# AD9854.net
KiCad netlist of a schematic drawn in Altium Designer
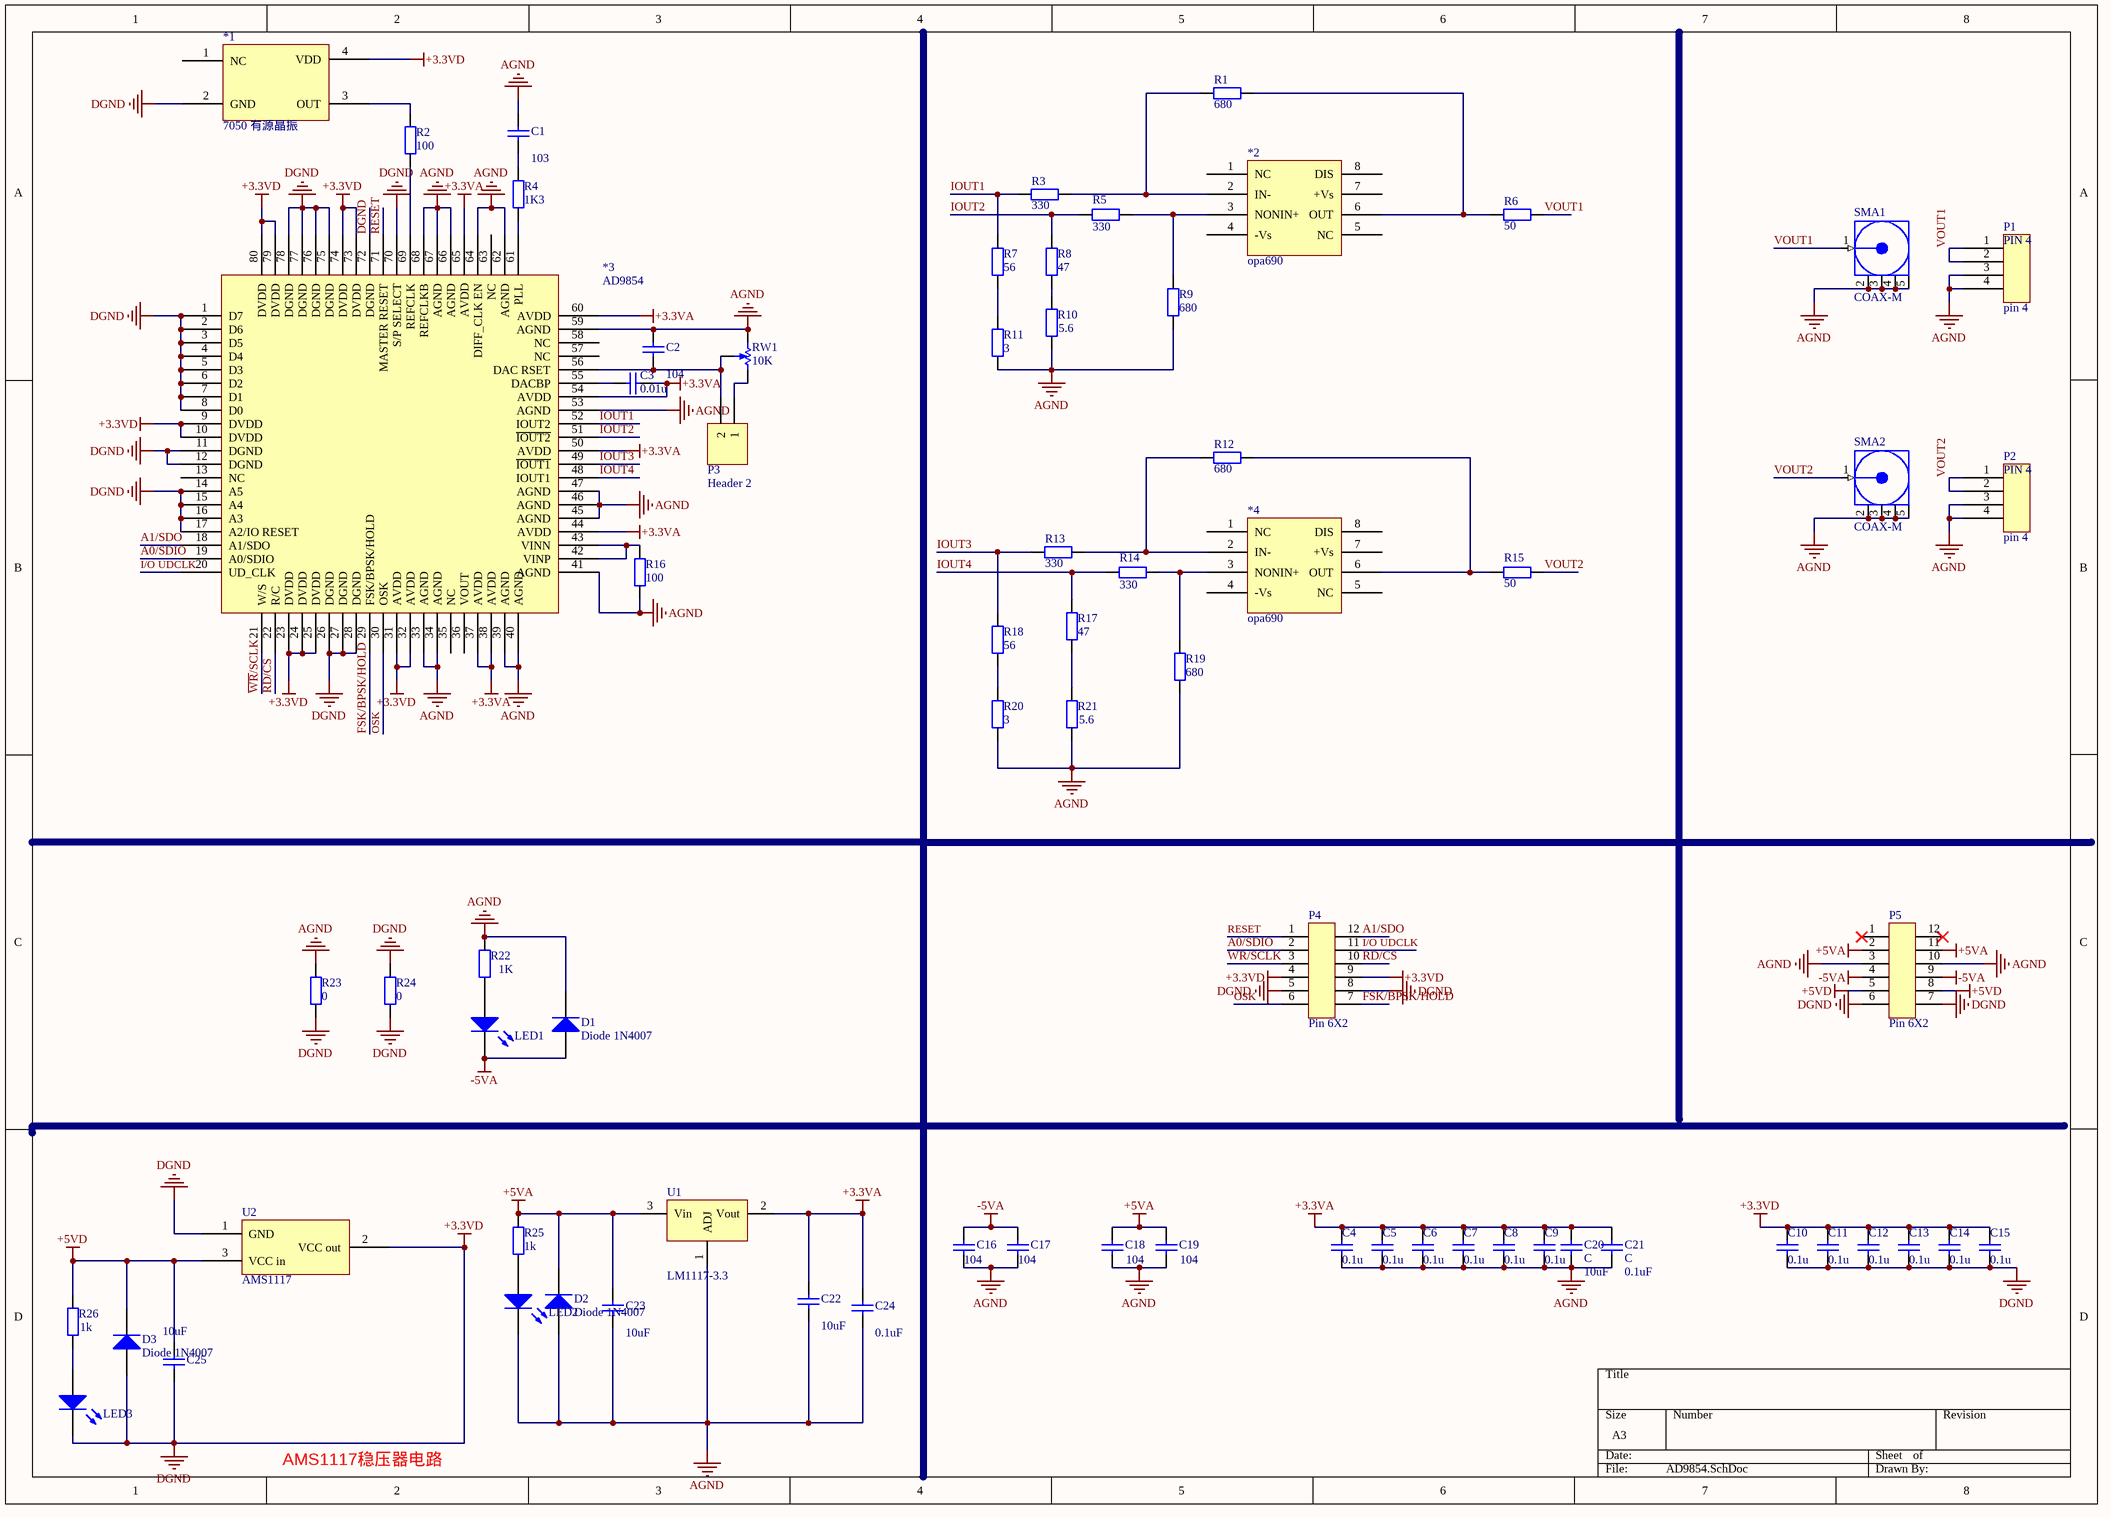
[diagram p0: AD9854.SchDoc]

(export (version "E")
  (design (tool "Eeschema 10.0.6"))
  (components
    (comp (ref "*1") (value "7050 有源晶振") (footprint "7050晶振") (libsource (lib "我的元件库") (part "7050 有源晶振")))
    (comp (ref "*2") (value "opa690") (footprint "OPA690") (libsource (lib "JC") (part "opa690")))
    (comp (ref "*3") (value "AD9854") (footprint "LPQF 80 9854") (libsource (lib "我的元件库") (part "AD9854")))
    (comp (ref "*4") (value "opa690") (footprint "OPA690") (libsource (lib "JC") (part "opa690")))
    (comp (ref "C1")
      (value "103")
      (footprint "C0603")
      (fields (field (name "Comment") "C"))
      (libsource (lib "我的元件库") (part "C"))
    )
    (comp (ref "C2")
      (value "104")
      (footprint "C0603")
      (fields (field (name "Comment") "C"))
      (libsource (lib "我的元件库") (part "C"))
    )
    (comp (ref "C3") (value "0.01u") (footprint "C0603") (libsource (lib "顶层SMD") (part "C_0805")))
    (comp (ref "C4") (value "0.1u") (footprint "C0603") (libsource (lib "顶层SMD") (part "C_0805")))
    (comp (ref "C5") (value "0.1u") (footprint "C0603") (libsource (lib "顶层SMD") (part "C_0805")))
    (comp (ref "C6") (value "0.1u") (footprint "C0603") (libsource (lib "顶层SMD") (part "C_0805")))
    (comp (ref "C7") (value "0.1u") (footprint "C0603") (libsource (lib "顶层SMD") (part "C_0805")))
    (comp (ref "C8") (value "0.1u") (footprint "C0603") (libsource (lib "顶层SMD") (part "C_0805")))
    (comp (ref "C9") (value "0.1u") (footprint "C0603") (libsource (lib "顶层SMD") (part "C_0805")))
    (comp (ref "C10") (value "0.1u") (footprint "C0603") (libsource (lib "顶层SMD") (part "C_0805")))
    (comp (ref "C11") (value "0.1u") (footprint "C0603") (libsource (lib "顶层SMD") (part "C_0805")))
    (comp (ref "C12") (value "0.1u") (footprint "C0603") (libsource (lib "顶层SMD") (part "C_0805")))
    (comp (ref "C13") (value "0.1u") (footprint "C0603") (libsource (lib "顶层SMD") (part "C_0805")))
    (comp (ref "C14") (value "0.1u") (footprint "C0603") (libsource (lib "顶层SMD") (part "C_0805")))
    (comp (ref "C15") (value "0.1u") (footprint "C0603") (libsource (lib "顶层SMD") (part "C_0805")))
    (comp (ref "C16")
      (value "104")
      (footprint "C0603")
      (fields (field (name "Comment") "C"))
      (libsource (lib "我的元件库") (part "C"))
    )
    (comp (ref "C17")
      (value "104")
      (footprint "C0603")
      (fields (field (name "Comment") "C"))
      (libsource (lib "我的元件库") (part "C"))
    )
    (comp (ref "C18")
      (value "104")
      (footprint "C0603")
      (fields (field (name "Comment") "C"))
      (libsource (lib "我的元件库") (part "C"))
    )
    (comp (ref "C19")
      (value "104")
      (footprint "C0603")
      (fields (field (name "Comment") "C"))
      (libsource (lib "我的元件库") (part "C"))
    )
    (comp (ref "C20")
      (value "C")
      (footprint "C0603")
      (fields (field (name "ALTIUM_VALUE") "10uF"))
      (libsource (lib "我的元件库") (part "C"))
    )
    (comp (ref "C21")
      (value "C")
      (footprint "C0603")
      (fields (field (name "ALTIUM_VALUE") "0.1uF"))
      (libsource (lib "我的元件库") (part "C"))
    )
    (comp (ref "C22")
      (value "10uF")
      (footprint "C0603")
      (fields (field (name "Comment") "C"))
      (libsource (lib "我的元件库") (part "C"))
    )
    (comp (ref "C23")
      (value "10uF")
      (footprint "C0603")
      (fields (field (name "Comment") "C"))
      (libsource (lib "我的元件库") (part "C"))
    )
    (comp (ref "C24")
      (value "0.1uF")
      (footprint "C0603")
      (fields (field (name "Comment") "C"))
      (libsource (lib "我的元件库") (part "C"))
    )
    (comp (ref "C25")
      (value "10uF")
      (footprint "C0603")
      (fields (field (name "Comment") "C"))
      (libsource (lib "我的元件库") (part "C"))
    )
    (comp (ref "D1")
      (value "Diode 1N4007")
      (footprint "二极管SMB")
      (description "1 Amp General Purpose Rectifier")
      (fields (field (name "PUBLISHER") "Altium Limited"))
      (libsource (lib "Miscellaneous Devices") (part "Diode 1N4007"))
    )
    (comp (ref "D2")
      (value "Diode 1N4007")
      (footprint "二极管SMB")
      (description "1 Amp General Purpose Rectifier")
      (fields (field (name "PUBLISHER") "Altium Limited"))
      (libsource (lib "Miscellaneous Devices") (part "Diode 1N4007"))
    )
    (comp (ref "D3")
      (value "Diode 1N4007")
      (footprint "二极管SMB")
      (description "1 Amp General Purpose Rectifier")
      (fields (field (name "PUBLISHER") "Altium Limited"))
      (libsource (lib "Miscellaneous Devices") (part "Diode 1N4007"))
    )
    (comp (ref "LED1") (value "LED") (footprint "C0603") (libsource (lib "我的元件库") (part "LED")))
    (comp (ref "LED2") (value "LED") (footprint "C0603") (libsource (lib "我的元件库") (part "LED")))
    (comp (ref "LED3") (value "LED") (footprint "C0603") (libsource (lib "我的元件库") (part "LED")))
    (comp (ref "P1") (value "pin 4") (footprint "pin 4") (libsource (lib "我的元件库") (part "pin 4")))
    (comp (ref "P2") (value "pin 4") (footprint "pin 4") (libsource (lib "我的元件库") (part "pin 4")))
    (comp (ref "P3")
      (value "Header 2")
      (footprint "HDR1X2")
      (description "Header, 2-Pin")
      (fields (field (name "PUBLISHER") "Altium Limited"))
      (libsource (lib "Miscellaneous Connectors") (part "Header 2"))
    )
    (comp (ref "P4") (value "Pin 6X2") (footprint "Pin 6X2") (libsource (lib "我的元件库") (part "Pin 6X2")))
    (comp (ref "P5") (value "Pin 6X2") (footprint "Pin 6X2") (libsource (lib "我的元件库") (part "Pin 6X2")))
    (comp (ref "R1")
      (value "680")
      (footprint "C0603")
      (fields (field (name "Comment") "R"))
      (libsource (lib "") (part "R_1"))
    )
    (comp (ref "R2")
      (value "100")
      (footprint "C0603")
      (fields (field (name "Comment") "R"))
      (libsource (lib "我的元件库") (part "R"))
    )
    (comp (ref "R3")
      (value "330")
      (footprint "C0603")
      (fields (field (name "Comment") "R"))
      (libsource (lib "") (part "R_1"))
    )
    (comp (ref "R4") (value "1K3") (footprint "C0603") (libsource (lib "顶层SMD") (part "R_0805")))
    (comp (ref "R5")
      (value "330")
      (footprint "C0603")
      (fields (field (name "Comment") "R"))
      (libsource (lib "") (part "R_1"))
    )
    (comp (ref "R6")
      (value "50")
      (footprint "C0603")
      (fields (field (name "Comment") "R"))
      (libsource (lib "") (part "R_1"))
    )
    (comp (ref "R7")
      (value "56")
      (footprint "C0603")
      (fields (field (name "Comment") "R"))
      (libsource (lib "我的元件库") (part "R"))
    )
    (comp (ref "R8")
      (value "47")
      (footprint "C0603")
      (fields (field (name "Comment") "R"))
      (libsource (lib "我的元件库") (part "R"))
    )
    (comp (ref "R9")
      (value "680")
      (footprint "C0603")
      (fields (field (name "Comment") "R"))
      (libsource (lib "我的元件库") (part "R"))
    )
    (comp (ref "R10")
      (value "5.6")
      (footprint "C0603")
      (fields (field (name "Comment") "R"))
      (libsource (lib "我的元件库") (part "R"))
    )
    (comp (ref "R11")
      (value "3")
      (footprint "C0603")
      (fields (field (name "Comment") "R"))
      (libsource (lib "我的元件库") (part "R"))
    )
    (comp (ref "R12")
      (value "680")
      (footprint "C0603")
      (fields (field (name "Comment") "R"))
      (libsource (lib "") (part "R_1"))
    )
    (comp (ref "R13")
      (value "330")
      (footprint "C0603")
      (fields (field (name "Comment") "R"))
      (libsource (lib "") (part "R_1"))
    )
    (comp (ref "R14")
      (value "330")
      (footprint "C0603")
      (fields (field (name "Comment") "R"))
      (libsource (lib "") (part "R_1"))
    )
    (comp (ref "R15")
      (value "50")
      (footprint "C0603")
      (fields (field (name "Comment") "R"))
      (libsource (lib "") (part "R_1"))
    )
    (comp (ref "R16")
      (value "100")
      (footprint "C0603")
      (fields (field (name "Comment") "R"))
      (libsource (lib "") (part "R_2"))
    )
    (comp (ref "R17")
      (value "47")
      (footprint "C0603")
      (fields (field (name "Comment") "R"))
      (libsource (lib "我的元件库") (part "R"))
    )
    (comp (ref "R18")
      (value "56")
      (footprint "C0603")
      (fields (field (name "Comment") "R"))
      (libsource (lib "我的元件库") (part "R"))
    )
    (comp (ref "R19")
      (value "680")
      (footprint "C0603")
      (fields (field (name "Comment") "R"))
      (libsource (lib "我的元件库") (part "R"))
    )
    (comp (ref "R20")
      (value "3")
      (footprint "C0603")
      (fields (field (name "Comment") "R"))
      (libsource (lib "我的元件库") (part "R"))
    )
    (comp (ref "R21")
      (value "5.6")
      (footprint "C0603")
      (fields (field (name "Comment") "R"))
      (libsource (lib "我的元件库") (part "R"))
    )
    (comp (ref "R22")
      (value "1K")
      (footprint "C0603")
      (fields (field (name "Comment") "R"))
      (libsource (lib "我的元件库") (part "R"))
    )
    (comp (ref "R23") (value "0") (footprint "C0603") (libsource (lib "顶层SMD") (part "R_0805")))
    (comp (ref "R24") (value "0") (footprint "C0603") (libsource (lib "顶层SMD") (part "R_0805")))
    (comp (ref "R25")
      (value "1k")
      (footprint "C0603")
      (fields (field (name "Comment") "R"))
      (libsource (lib "我的元件库") (part "R"))
    )
    (comp (ref "R26")
      (value "1k")
      (footprint "C0603")
      (fields (field (name "Comment") "R"))
      (libsource (lib "我的元件库") (part "R"))
    )
    (comp (ref "RW1")
      (value "10K")
      (footprint "电位器")
      (fields (field (name "Comment") "R"))
      (libsource (lib "我的元件库") (part "电位器"))
    )
    (comp (ref "SMA1")
      (value "COAX-M")
      (footprint "SMB_V-RJ45")
      (description "RF Coaxial PCB Connector, MMCX; Thru-Hole, Vertical Mount Plug,  50 Ohm Impedance")
      (fields (field (name "PUBLISHER") "Altium Limited"))
      (libsource (lib "Miscellaneous Connectors") (part "COAX-M"))
    )
    (comp (ref "SMA2")
      (value "COAX-M")
      (footprint "SMB_V-RJ45")
      (description "RF Coaxial PCB Connector, MMCX; Thru-Hole, Vertical Mount Plug,  50 Ohm Impedance")
      (fields (field (name "PUBLISHER") "Altium Limited"))
      (libsource (lib "Miscellaneous Connectors") (part "COAX-M"))
    )
    (comp (ref "U1") (value "LM1117-3.3") (footprint "LM78**") (libsource (lib "我的元件库") (part "LM317")))
    (comp (ref "U2") (value "AMS1117") (footprint "AMS1117") (libsource (lib "我的元件库") (part "AMS1117")))
  )
  (nets
    (net (code "1") (name "+3.3VA") (class "Default")
      (node (ref "*3") (pin "37") (pinfunction "AVDD_37") (pintype "passive"))
      (node (ref "*3") (pin "38") (pinfunction "AVDD_38") (pintype "passive"))
      (node (ref "*3") (pin "44") (pinfunction "AVDD_44") (pintype "passive"))
      (node (ref "*3") (pin "50") (pinfunction "AVDD_50") (pintype "passive"))
      (node (ref "*3") (pin "54") (pinfunction "AVDD_54") (pintype "passive"))
      (node (ref "*3") (pin "60") (pinfunction "AVDD_60") (pintype "passive"))
      (node (ref "*3") (pin "65") (pinfunction "AVDD_65") (pintype "passive"))
      (node (ref "C20") (pin "2") (pinfunction "2_2") (pintype "passive"))
      (node (ref "C21") (pin "2") (pinfunction "2_2") (pintype "passive"))
      (node (ref "C22") (pin "2") (pinfunction "2_2") (pintype "passive"))
      (node (ref "C24") (pin "2") (pinfunction "2_2") (pintype "passive"))
      (node (ref "C3") (pin "1") (pinfunction "1_1") (pintype "passive"))
      (node (ref "C4") (pin "2") (pinfunction "2_2") (pintype "passive"))
      (node (ref "C5") (pin "2") (pinfunction "2_2") (pintype "passive"))
      (node (ref "C6") (pin "2") (pinfunction "2_2") (pintype "passive"))
      (node (ref "C7") (pin "2") (pinfunction "2_2") (pintype "passive"))
      (node (ref "C8") (pin "2") (pinfunction "2_2") (pintype "passive"))
      (node (ref "C9") (pin "2") (pinfunction "2_2") (pintype "passive"))
      (node (ref "U1") (pin "2") (pinfunction "Vout_2") (pintype "passive"))
    )
    (net (code "2") (name "+3.3VD") (class "Default")
      (node (ref "*1") (pin "2") (pinfunction "GND_2") (pintype "passive"))
      (node (ref "*1") (pin "4") (pinfunction "VDD_4") (pintype "passive"))
      (node (ref "*3") (pin "1") (pinfunction "D7_1") (pintype "passive"))
      (node (ref "*3") (pin "10") (pinfunction "DVDD_10") (pintype "passive"))
      (node (ref "*3") (pin "11") (pinfunction "DGND_11") (pintype "passive"))
      (node (ref "*3") (pin "12") (pinfunction "DGND_12") (pintype "passive"))
      (node (ref "*3") (pin "14") (pinfunction "A5_14") (pintype "passive"))
      (node (ref "*3") (pin "15") (pinfunction "A4_15") (pintype "passive"))
      (node (ref "*3") (pin "16") (pinfunction "A3_16") (pintype "passive"))
      (node (ref "*3") (pin "17") (pinfunction "A2/IO_RESET_17") (pintype "passive"))
      (node (ref "*3") (pin "2") (pinfunction "D6_2") (pintype "passive"))
      (node (ref "*3") (pin "23") (pinfunction "DVDD_23") (pintype "passive"))
      (node (ref "*3") (pin "24") (pinfunction "DVDD_24") (pintype "passive"))
      (node (ref "*3") (pin "25") (pinfunction "DVDD_25") (pintype "passive"))
      (node (ref "*3") (pin "26") (pinfunction "DGND_26") (pintype "passive"))
      (node (ref "*3") (pin "27") (pinfunction "DGND_27") (pintype "passive"))
      (node (ref "*3") (pin "28") (pinfunction "DGND_28") (pintype "passive"))
      (node (ref "*3") (pin "3") (pinfunction "D5_3") (pintype "passive"))
      (node (ref "*3") (pin "31") (pinfunction "AVDD_31") (pintype "passive"))
      (node (ref "*3") (pin "32") (pinfunction "AVDD_32") (pintype "passive"))
      (node (ref "*3") (pin "4") (pinfunction "D4_4") (pintype "passive"))
      (node (ref "*3") (pin "5") (pinfunction "D3_5") (pintype "passive"))
      (node (ref "*3") (pin "6") (pinfunction "D2_6") (pintype "passive"))
      (node (ref "*3") (pin "7") (pinfunction "D1_7") (pintype "passive"))
      (node (ref "*3") (pin "70") (pinfunction "S/P_SELECT_70") (pintype "passive"))
      (node (ref "*3") (pin "72") (pinfunction "DGND_72") (pintype "passive"))
      (node (ref "*3") (pin "73") (pinfunction "DVDD_73") (pintype "passive"))
      (node (ref "*3") (pin "74") (pinfunction "DVDD_74") (pintype "passive"))
      (node (ref "*3") (pin "75") (pinfunction "DGND_75") (pintype "passive"))
      (node (ref "*3") (pin "76") (pinfunction "DGND_76") (pintype "passive"))
      (node (ref "*3") (pin "77") (pinfunction "DGND_77") (pintype "passive"))
      (node (ref "*3") (pin "78") (pinfunction "DGND_78") (pintype "passive"))
      (node (ref "*3") (pin "79") (pinfunction "DVDD_79") (pintype "passive"))
      (node (ref "*3") (pin "8") (pinfunction "D0_8") (pintype "passive"))
      (node (ref "*3") (pin "80") (pinfunction "DVDD_80") (pintype "passive"))
      (node (ref "*3") (pin "9") (pinfunction "DVDD_9") (pintype "passive"))
      (node (ref "C10") (pin "1") (pinfunction "1_1") (pintype "passive"))
      (node (ref "C10") (pin "2") (pinfunction "2_2") (pintype "passive"))
      (node (ref "C11") (pin "1") (pinfunction "1_1") (pintype "passive"))
      (node (ref "C11") (pin "2") (pinfunction "2_2") (pintype "passive"))
      (node (ref "C12") (pin "1") (pinfunction "1_1") (pintype "passive"))
      (node (ref "C12") (pin "2") (pinfunction "2_2") (pintype "passive"))
      (node (ref "C13") (pin "1") (pinfunction "1_1") (pintype "passive"))
      (node (ref "C13") (pin "2") (pinfunction "2_2") (pintype "passive"))
      (node (ref "C14") (pin "1") (pinfunction "1_1") (pintype "passive"))
      (node (ref "C14") (pin "2") (pinfunction "2_2") (pintype "passive"))
      (node (ref "C15") (pin "1") (pinfunction "1_1") (pintype "passive"))
      (node (ref "C15") (pin "2") (pinfunction "2_2") (pintype "passive"))
      (node (ref "C25") (pin "2") (pinfunction "2_2") (pintype "passive"))
      (node (ref "D3") (pin "1") (pinfunction "A_1") (pintype "passive"))
      (node (ref "LED3") (pin "2") (pinfunction "K_2") (pintype "passive"))
      (node (ref "P4") (pin "4") (pinfunction "4_4") (pintype "passive"))
      (node (ref "P4") (pin "5") (pinfunction "5_5") (pintype "passive"))
      (node (ref "P4") (pin "8") (pinfunction "8_8") (pintype "passive"))
      (node (ref "P4") (pin "9") (pinfunction "9_9") (pintype "passive"))
      (node (ref "P5") (pin "6") (pinfunction "6_6") (pintype "passive"))
      (node (ref "P5") (pin "7") (pinfunction "7_7") (pintype "passive"))
      (node (ref "R23") (pin "1") (pinfunction "1_1") (pintype "passive"))
      (node (ref "R24") (pin "1") (pinfunction "1_1") (pintype "passive"))
      (node (ref "R24") (pin "2") (pinfunction "2_2") (pintype "passive"))
      (node (ref "U2") (pin "1") (pinfunction "GND_1") (pintype "power_in"))
      (node (ref "U2") (pin "2") (pinfunction "VCC_out_2") (pintype "power_in"))
    )
    (net (code "3") (name "+5VA") (class "Default")
      (node (ref "C18") (pin "2") (pinfunction "2_2") (pintype "passive"))
      (node (ref "C19") (pin "2") (pinfunction "2_2") (pintype "passive"))
      (node (ref "C23") (pin "2") (pinfunction "2_2") (pintype "passive"))
      (node (ref "D2") (pin "2") (pinfunction "K_2") (pintype "passive"))
      (node (ref "P5") (pin "11") (pinfunction "11_11") (pintype "passive"))
      (node (ref "P5") (pin "2") (pinfunction "2_2") (pintype "passive"))
      (node (ref "R25") (pin "2") (pinfunction "2_2") (pintype "passive"))
      (node (ref "U1") (pin "3") (pinfunction "Vin_3") (pintype "passive"))
    )
    (net (code "4") (name "+5VD") (class "Default")
      (node (ref "C25") (pin "1") (pinfunction "1_1") (pintype "passive"))
      (node (ref "D3") (pin "2") (pinfunction "K_2") (pintype "passive"))
      (node (ref "P5") (pin "5") (pinfunction "5_5") (pintype "passive"))
      (node (ref "P5") (pin "8") (pinfunction "8_8") (pintype "passive"))
      (node (ref "R26") (pin "2") (pinfunction "2_2") (pintype "passive"))
      (node (ref "U2") (pin "3") (pinfunction "VCC_in_3") (pintype "power_in"))
    )
    (net (code "5") (name "-5VA") (class "Default")
      (node (ref "C16") (pin "2") (pinfunction "2_2") (pintype "passive"))
      (node (ref "C17") (pin "2") (pinfunction "2_2") (pintype "passive"))
      (node (ref "D1") (pin "1") (pinfunction "A_1") (pintype "passive"))
      (node (ref "LED1") (pin "2") (pinfunction "K_2") (pintype "passive"))
      (node (ref "P5") (pin "4") (pinfunction "4_4") (pintype "passive"))
      (node (ref "P5") (pin "9") (pinfunction "9_9") (pintype "passive"))
    )
    (net (code "6") (name "/A0{slash}SDIO") (class "Default")
      (node (ref "*3") (pin "19") (pinfunction "A0/SDIO_19") (pintype "passive"))
      (node (ref "P4") (pin "2") (pinfunction "2_2") (pintype "passive"))
    )
    (net (code "7") (name "/A1{slash}SDO") (class "Default")
      (node (ref "*3") (pin "18") (pinfunction "A1/SDO_18") (pintype "passive"))
      (node (ref "P4") (pin "12") (pinfunction "12_12") (pintype "passive"))
    )
    (net (code "8") (name "/FSK{slash}BPSK{slash}HOLD") (class "Default")
      (node (ref "*3") (pin "29") (pinfunction "FSK/BPSK/HOLD_29") (pintype "passive"))
      (node (ref "P4") (pin "7") (pinfunction "7_7") (pintype "passive"))
    )
    (net (code "9") (name "/IOUT1") (class "Default")
      (node (ref "*3") (pin "52") (pinfunction "IOUT2_52") (pintype "passive"))
      (node (ref "R3") (pin "1") (pinfunction "1_1") (pintype "passive"))
      (node (ref "R7") (pin "2") (pinfunction "2_2") (pintype "passive"))
    )
    (net (code "10") (name "/IOUT2") (class "Default")
      (node (ref "*3") (pin "51") (pinfunction "~{IOUT2}_51") (pintype "passive"))
      (node (ref "R5") (pin "1") (pinfunction "1_1") (pintype "passive"))
      (node (ref "R8") (pin "2") (pinfunction "2_2") (pintype "passive"))
    )
    (net (code "11") (name "/IOUT3") (class "Default")
      (node (ref "*3") (pin "49") (pinfunction "~{IOUT1}_49") (pintype "passive"))
      (node (ref "R13") (pin "1") (pinfunction "1_1") (pintype "passive"))
      (node (ref "R18") (pin "2") (pinfunction "2_2") (pintype "passive"))
    )
    (net (code "12") (name "/IOUT4") (class "Default")
      (node (ref "*3") (pin "48") (pinfunction "IOUT1_48") (pintype "passive"))
      (node (ref "R14") (pin "1") (pinfunction "1_1") (pintype "passive"))
      (node (ref "R17") (pin "2") (pinfunction "2_2") (pintype "passive"))
    )
    (net (code "13") (name "/I{slash}O UDCLK") (class "Default")
      (node (ref "*3") (pin "20") (pinfunction "UD_CLK_20") (pintype "passive"))
      (node (ref "P4") (pin "11") (pinfunction "11_11") (pintype "passive"))
    )
    (net (code "14") (name "/OSK") (class "Default")
      (node (ref "*3") (pin "30") (pinfunction "OSK_30") (pintype "passive"))
      (node (ref "P4") (pin "6") (pinfunction "6_6") (pintype "passive"))
    )
    (net (code "15") (name "/RESET") (class "Default")
      (node (ref "*3") (pin "71") (pinfunction "MASTER_RESET_71") (pintype "passive"))
      (node (ref "P4") (pin "1") (pinfunction "1_1") (pintype "passive"))
    )
    (net (code "16") (name "/VOUT1") (class "Default")
      (node (ref "P1") (pin "1") (pintype "passive"))
      (node (ref "P1") (pin "2") (pintype "passive"))
      (node (ref "R6") (pin "2") (pinfunction "2_2") (pintype "passive"))
      (node (ref "SMA1") (pin "1") (pinfunction "Signal_1") (pintype "input"))
    )
    (net (code "17") (name "/VOUT2") (class "Default")
      (node (ref "P2") (pin "1") (pintype "passive"))
      (node (ref "P2") (pin "2") (pintype "passive"))
      (node (ref "R15") (pin "2") (pinfunction "2_2") (pintype "passive"))
      (node (ref "SMA2") (pin "1") (pinfunction "Signal_1") (pintype "input"))
    )
    (net (code "18") (name "/~{RD}{slash}~{CS}") (class "Default")
      (node (ref "*3") (pin "22") (pinfunction "R/C_22") (pintype "passive"))
      (node (ref "P4") (pin "10") (pinfunction "10_10") (pintype "passive"))
    )
    (net (code "19") (name "/~{WR}{slash}SCLK") (class "Default")
      (node (ref "*3") (pin "21") (pinfunction "W/S_21") (pintype "passive"))
      (node (ref "P4") (pin "3") (pinfunction "3_3") (pintype "passive"))
    )
    (net (code "20") (name "AGND") (class "Default")
      (node (ref "*3") (pin "33") (pinfunction "AGND_33") (pintype "passive"))
      (node (ref "*3") (pin "34") (pinfunction "AGND_34") (pintype "passive"))
      (node (ref "*3") (pin "39") (pinfunction "AGND_39") (pintype "passive"))
      (node (ref "*3") (pin "40") (pinfunction "AGND_40") (pintype "passive"))
      (node (ref "*3") (pin "41") (pinfunction "AGND_41") (pintype "passive"))
      (node (ref "*3") (pin "45") (pinfunction "AGND_45") (pintype "passive"))
      (node (ref "*3") (pin "46") (pinfunction "AGND_46") (pintype "passive"))
      (node (ref "*3") (pin "47") (pinfunction "AGND_47") (pintype "passive"))
      (node (ref "*3") (pin "53") (pinfunction "AGND_53") (pintype "passive"))
      (node (ref "*3") (pin "59") (pinfunction "AGND_59") (pintype "passive"))
      (node (ref "*3") (pin "62") (pinfunction "AGND_62") (pintype "passive"))
      (node (ref "*3") (pin "64") (pinfunction "DIFF_CLK_EN_64") (pintype "passive"))
      (node (ref "*3") (pin "66") (pinfunction "AGND_66") (pintype "passive"))
      (node (ref "*3") (pin "67") (pinfunction "AGND_67") (pintype "passive"))
      (node (ref "*3") (pin "68") (pinfunction "REFCLKB_68") (pintype "passive"))
      (node (ref "C1") (pin "2") (pinfunction "2_2") (pintype "passive"))
      (node (ref "C16") (pin "1") (pinfunction "1_1") (pintype "passive"))
      (node (ref "C17") (pin "1") (pinfunction "1_1") (pintype "passive"))
      (node (ref "C18") (pin "1") (pinfunction "1_1") (pintype "passive"))
      (node (ref "C19") (pin "1") (pinfunction "1_1") (pintype "passive"))
      (node (ref "C2") (pin "2") (pinfunction "2_2") (pintype "passive"))
      (node (ref "C20") (pin "1") (pinfunction "1_1") (pintype "passive"))
      (node (ref "C21") (pin "1") (pinfunction "1_1") (pintype "passive"))
      (node (ref "C22") (pin "1") (pinfunction "1_1") (pintype "passive"))
      (node (ref "C23") (pin "1") (pinfunction "1_1") (pintype "passive"))
      (node (ref "C24") (pin "1") (pinfunction "1_1") (pintype "passive"))
      (node (ref "C4") (pin "1") (pinfunction "1_1") (pintype "passive"))
      (node (ref "C5") (pin "1") (pinfunction "1_1") (pintype "passive"))
      (node (ref "C6") (pin "1") (pinfunction "1_1") (pintype "passive"))
      (node (ref "C7") (pin "1") (pinfunction "1_1") (pintype "passive"))
      (node (ref "C8") (pin "1") (pinfunction "1_1") (pintype "passive"))
      (node (ref "C9") (pin "1") (pinfunction "1_1") (pintype "passive"))
      (node (ref "D1") (pin "2") (pinfunction "K_2") (pintype "passive"))
      (node (ref "D2") (pin "1") (pinfunction "A_1") (pintype "passive"))
      (node (ref "LED2") (pin "2") (pinfunction "K_2") (pintype "passive"))
      (node (ref "P1") (pin "3") (pintype "passive"))
      (node (ref "P1") (pin "4") (pintype "passive"))
      (node (ref "P2") (pin "3") (pintype "passive"))
      (node (ref "P2") (pin "4") (pintype "passive"))
      (node (ref "P5") (pin "10") (pinfunction "10_10") (pintype "passive"))
      (node (ref "P5") (pin "3") (pinfunction "3_3") (pintype "passive"))
      (node (ref "R10") (pin "1") (pinfunction "1_1") (pintype "passive"))
      (node (ref "R11") (pin "1") (pinfunction "1_1") (pintype "passive"))
      (node (ref "R16") (pin "2") (pinfunction "2_2") (pintype "passive"))
      (node (ref "R19") (pin "1") (pinfunction "1_1") (pintype "passive"))
      (node (ref "R20") (pin "1") (pinfunction "1_1") (pintype "passive"))
      (node (ref "R21") (pin "1") (pinfunction "1_1") (pintype "passive"))
      (node (ref "R22") (pin "2") (pinfunction "2_2") (pintype "passive"))
      (node (ref "R23") (pin "2") (pinfunction "2_2") (pintype "passive"))
      (node (ref "R9") (pin "1") (pinfunction "1_1") (pintype "passive"))
      (node (ref "RW1") (pin "3") (pinfunction "-_3") (pintype "passive"))
      (node (ref "SMA1") (pin "2") (pinfunction "GND_2") (pintype "power_in"))
      (node (ref "SMA1") (pin "3") (pinfunction "GND_3") (pintype "power_in"))
      (node (ref "SMA1") (pin "4") (pinfunction "GND_4") (pintype "power_in"))
      (node (ref "SMA1") (pin "5") (pinfunction "GND_5") (pintype "power_in"))
      (node (ref "SMA2") (pin "2") (pinfunction "GND_2") (pintype "power_in"))
      (node (ref "SMA2") (pin "3") (pinfunction "GND_3") (pintype "power_in"))
      (node (ref "SMA2") (pin "4") (pinfunction "GND_4") (pintype "power_in"))
      (node (ref "SMA2") (pin "5") (pinfunction "GND_5") (pintype "power_in"))
      (node (ref "U1") (pin "1") (pinfunction "ADJ_1") (pintype "passive"))
    )
    (net (code "21") (name "Net-(*1-OUT)") (class "Default")
      (node (ref "*1") (pin "3") (pinfunction "OUT_3") (pintype "passive"))
      (node (ref "R2") (pin "2") (pinfunction "2_2") (pintype "passive"))
    )
    (net (code "22") (name "Net-(*2-IN-)") (class "Default")
      (node (ref "*2") (pin "2") (pinfunction "IN-_2") (pintype "passive"))
      (node (ref "R1") (pin "1") (pinfunction "1_1") (pintype "passive"))
      (node (ref "R3") (pin "2") (pinfunction "2_2") (pintype "passive"))
    )
    (net (code "23") (name "Net-(*2-NONIN+)") (class "Default")
      (node (ref "*2") (pin "3") (pinfunction "NONIN+_3") (pintype "passive"))
      (node (ref "R5") (pin "2") (pinfunction "2_2") (pintype "passive"))
      (node (ref "R9") (pin "2") (pinfunction "2_2") (pintype "passive"))
    )
    (net (code "24") (name "Net-(*2-OUT)") (class "Default")
      (node (ref "*2") (pin "6") (pinfunction "OUT_6") (pintype "passive"))
      (node (ref "R1") (pin "2") (pinfunction "2_2") (pintype "passive"))
      (node (ref "R6") (pin "1") (pinfunction "1_1") (pintype "passive"))
    )
    (net (code "25") (name "Net-(*3-DACBP)") (class "Default")
      (node (ref "*3") (pin "55") (pinfunction "DACBP_55") (pintype "passive"))
      (node (ref "C3") (pin "2") (pinfunction "2_2") (pintype "passive"))
    )
    (net (code "26") (name "Net-(*3-DAC_RSET)") (class "Default")
      (node (ref "*3") (pin "56") (pinfunction "DAC_RSET_56") (pintype "passive"))
      (node (ref "C2") (pin "1") (pinfunction "1_1") (pintype "passive"))
      (node (ref "P3") (pin "2") (pinfunction "2_2") (pintype "passive"))
      (node (ref "RW1") (pin "2") (pinfunction "W_2") (pintype "passive"))
    )
    (net (code "27") (name "Net-(*3-PLL)") (class "Default")
      (node (ref "*3") (pin "61") (pinfunction "PLL_61") (pintype "passive"))
      (node (ref "R4") (pin "1") (pinfunction "1_1") (pintype "passive"))
    )
    (net (code "28") (name "Net-(*3-REFCLK)") (class "Default")
      (node (ref "*3") (pin "69") (pinfunction "REFCLK_69") (pintype "passive"))
      (node (ref "R2") (pin "1") (pinfunction "1_1") (pintype "passive"))
    )
    (net (code "29") (name "Net-(*3-VINN)") (class "Default")
      (node (ref "*3") (pin "42") (pinfunction "VINP_42") (pintype "passive"))
      (node (ref "*3") (pin "43") (pinfunction "VINN_43") (pintype "passive"))
      (node (ref "R16") (pin "1") (pinfunction "1_1") (pintype "passive"))
    )
    (net (code "30") (name "Net-(*4-IN-)") (class "Default")
      (node (ref "*4") (pin "2") (pinfunction "IN-_2") (pintype "passive"))
      (node (ref "R12") (pin "1") (pinfunction "1_1") (pintype "passive"))
      (node (ref "R13") (pin "2") (pinfunction "2_2") (pintype "passive"))
    )
    (net (code "31") (name "Net-(*4-NONIN+)") (class "Default")
      (node (ref "*4") (pin "3") (pinfunction "NONIN+_3") (pintype "passive"))
      (node (ref "R14") (pin "2") (pinfunction "2_2") (pintype "passive"))
      (node (ref "R19") (pin "2") (pinfunction "2_2") (pintype "passive"))
    )
    (net (code "32") (name "Net-(*4-OUT)") (class "Default")
      (node (ref "*4") (pin "6") (pinfunction "OUT_6") (pintype "passive"))
      (node (ref "R12") (pin "2") (pinfunction "2_2") (pintype "passive"))
      (node (ref "R15") (pin "1") (pinfunction "1_1") (pintype "passive"))
    )
    (net (code "33") (name "Net-(C1-Pad1)") (class "Default")
      (node (ref "C1") (pin "1") (pinfunction "1_1") (pintype "passive"))
      (node (ref "R4") (pin "2") (pinfunction "2_2") (pintype "passive"))
    )
    (net (code "34") (name "Net-(LED1-A)") (class "Default")
      (node (ref "LED1") (pin "1") (pinfunction "A_1") (pintype "passive"))
      (node (ref "R22") (pin "1") (pinfunction "1_1") (pintype "passive"))
    )
    (net (code "35") (name "Net-(LED2-A)") (class "Default")
      (node (ref "LED2") (pin "1") (pinfunction "A_1") (pintype "passive"))
      (node (ref "R25") (pin "1") (pinfunction "1_1") (pintype "passive"))
    )
    (net (code "36") (name "Net-(LED3-A)") (class "Default")
      (node (ref "LED3") (pin "1") (pinfunction "A_1") (pintype "passive"))
      (node (ref "R26") (pin "1") (pinfunction "1_1") (pintype "passive"))
    )
    (net (code "37") (name "Net-(R10-Pad2)") (class "Default")
      (node (ref "R10") (pin "2") (pinfunction "2_2") (pintype "passive"))
      (node (ref "R8") (pin "1") (pinfunction "1_1") (pintype "passive"))
    )
    (net (code "38") (name "Net-(R11-Pad2)") (class "Default")
      (node (ref "R11") (pin "2") (pinfunction "2_2") (pintype "passive"))
      (node (ref "R7") (pin "1") (pinfunction "1_1") (pintype "passive"))
    )
    (net (code "39") (name "Net-(R17-Pad1)") (class "Default")
      (node (ref "R17") (pin "1") (pinfunction "1_1") (pintype "passive"))
      (node (ref "R21") (pin "2") (pinfunction "2_2") (pintype "passive"))
    )
    (net (code "40") (name "Net-(R18-Pad1)") (class "Default")
      (node (ref "R18") (pin "1") (pinfunction "1_1") (pintype "passive"))
      (node (ref "R20") (pin "2") (pinfunction "2_2") (pintype "passive"))
    )
    (net (code "41") (name "Net-(RW1-+)") (class "Default")
      (node (ref "P3") (pin "1") (pinfunction "1_1") (pintype "passive"))
      (node (ref "RW1") (pin "1") (pinfunction "+_1") (pintype "passive"))
    )
    (net (code "42") (name "unconnected-(*1-NC-Pad1)") (class "Default")
      (node (ref "*1") (pin "1") (pinfunction "NC_1") (pintype "passive"))
    )
    (net (code "43") (name "unconnected-(*2-+Vs-Pad7)") (class "Default")
      (node (ref "*2") (pin "7") (pinfunction "+Vs_7") (pintype "passive"))
    )
    (net (code "44") (name "unconnected-(*2--Vs-Pad4)") (class "Default")
      (node (ref "*2") (pin "4") (pinfunction "-Vs_4") (pintype "passive"))
    )
    (net (code "45") (name "unconnected-(*2-DIS-Pad8)") (class "Default")
      (node (ref "*2") (pin "8") (pinfunction "DIS_8") (pintype "passive"))
    )
    (net (code "46") (name "unconnected-(*2-NC-Pad1)") (class "Default")
      (node (ref "*2") (pin "1") (pinfunction "NC_1") (pintype "passive"))
    )
    (net (code "47") (name "unconnected-(*2-NC-Pad5)") (class "Default")
      (node (ref "*2") (pin "5") (pinfunction "NC_5") (pintype "passive"))
    )
    (net (code "48") (name "unconnected-(*3-NC-Pad13)") (class "Default")
      (node (ref "*3") (pin "13") (pinfunction "NC_13") (pintype "passive"))
    )
    (net (code "49") (name "unconnected-(*3-NC-Pad35)") (class "Default")
      (node (ref "*3") (pin "35") (pinfunction "NC_35") (pintype "passive"))
    )
    (net (code "50") (name "unconnected-(*3-NC-Pad57)") (class "Default")
      (node (ref "*3") (pin "57") (pinfunction "NC_57") (pintype "passive"))
    )
    (net (code "51") (name "unconnected-(*3-NC-Pad58)") (class "Default")
      (node (ref "*3") (pin "58") (pinfunction "NC_58") (pintype "passive"))
    )
    (net (code "52") (name "unconnected-(*3-NC-Pad63)") (class "Default")
      (node (ref "*3") (pin "63") (pinfunction "NC_63") (pintype "passive"))
    )
    (net (code "53") (name "unconnected-(*3-VOUT-Pad36)") (class "Default")
      (node (ref "*3") (pin "36") (pinfunction "VOUT_36") (pintype "passive"))
    )
    (net (code "54") (name "unconnected-(*4-+Vs-Pad7)") (class "Default")
      (node (ref "*4") (pin "7") (pinfunction "+Vs_7") (pintype "passive"))
    )
    (net (code "55") (name "unconnected-(*4--Vs-Pad4)") (class "Default")
      (node (ref "*4") (pin "4") (pinfunction "-Vs_4") (pintype "passive"))
    )
    (net (code "56") (name "unconnected-(*4-DIS-Pad8)") (class "Default")
      (node (ref "*4") (pin "8") (pinfunction "DIS_8") (pintype "passive"))
    )
    (net (code "57") (name "unconnected-(*4-NC-Pad1)") (class "Default")
      (node (ref "*4") (pin "1") (pinfunction "NC_1") (pintype "passive"))
    )
    (net (code "58") (name "unconnected-(*4-NC-Pad5)") (class "Default")
      (node (ref "*4") (pin "5") (pinfunction "NC_5") (pintype "passive"))
    )
    (net (code "59") (name "unconnected-(P5-Pad1)") (class "Default")
      (node (ref "P5") (pin "1") (pinfunction "1_1") (pintype "passive+no_connect"))
    )
    (net (code "60") (name "unconnected-(P5-Pad12)") (class "Default")
      (node (ref "P5") (pin "12") (pinfunction "12_12") (pintype "passive+no_connect"))
    )
  )
)
